# XBee_Explorer_Thin.net
KiCad netlist of a schematic drawn in EAGLE
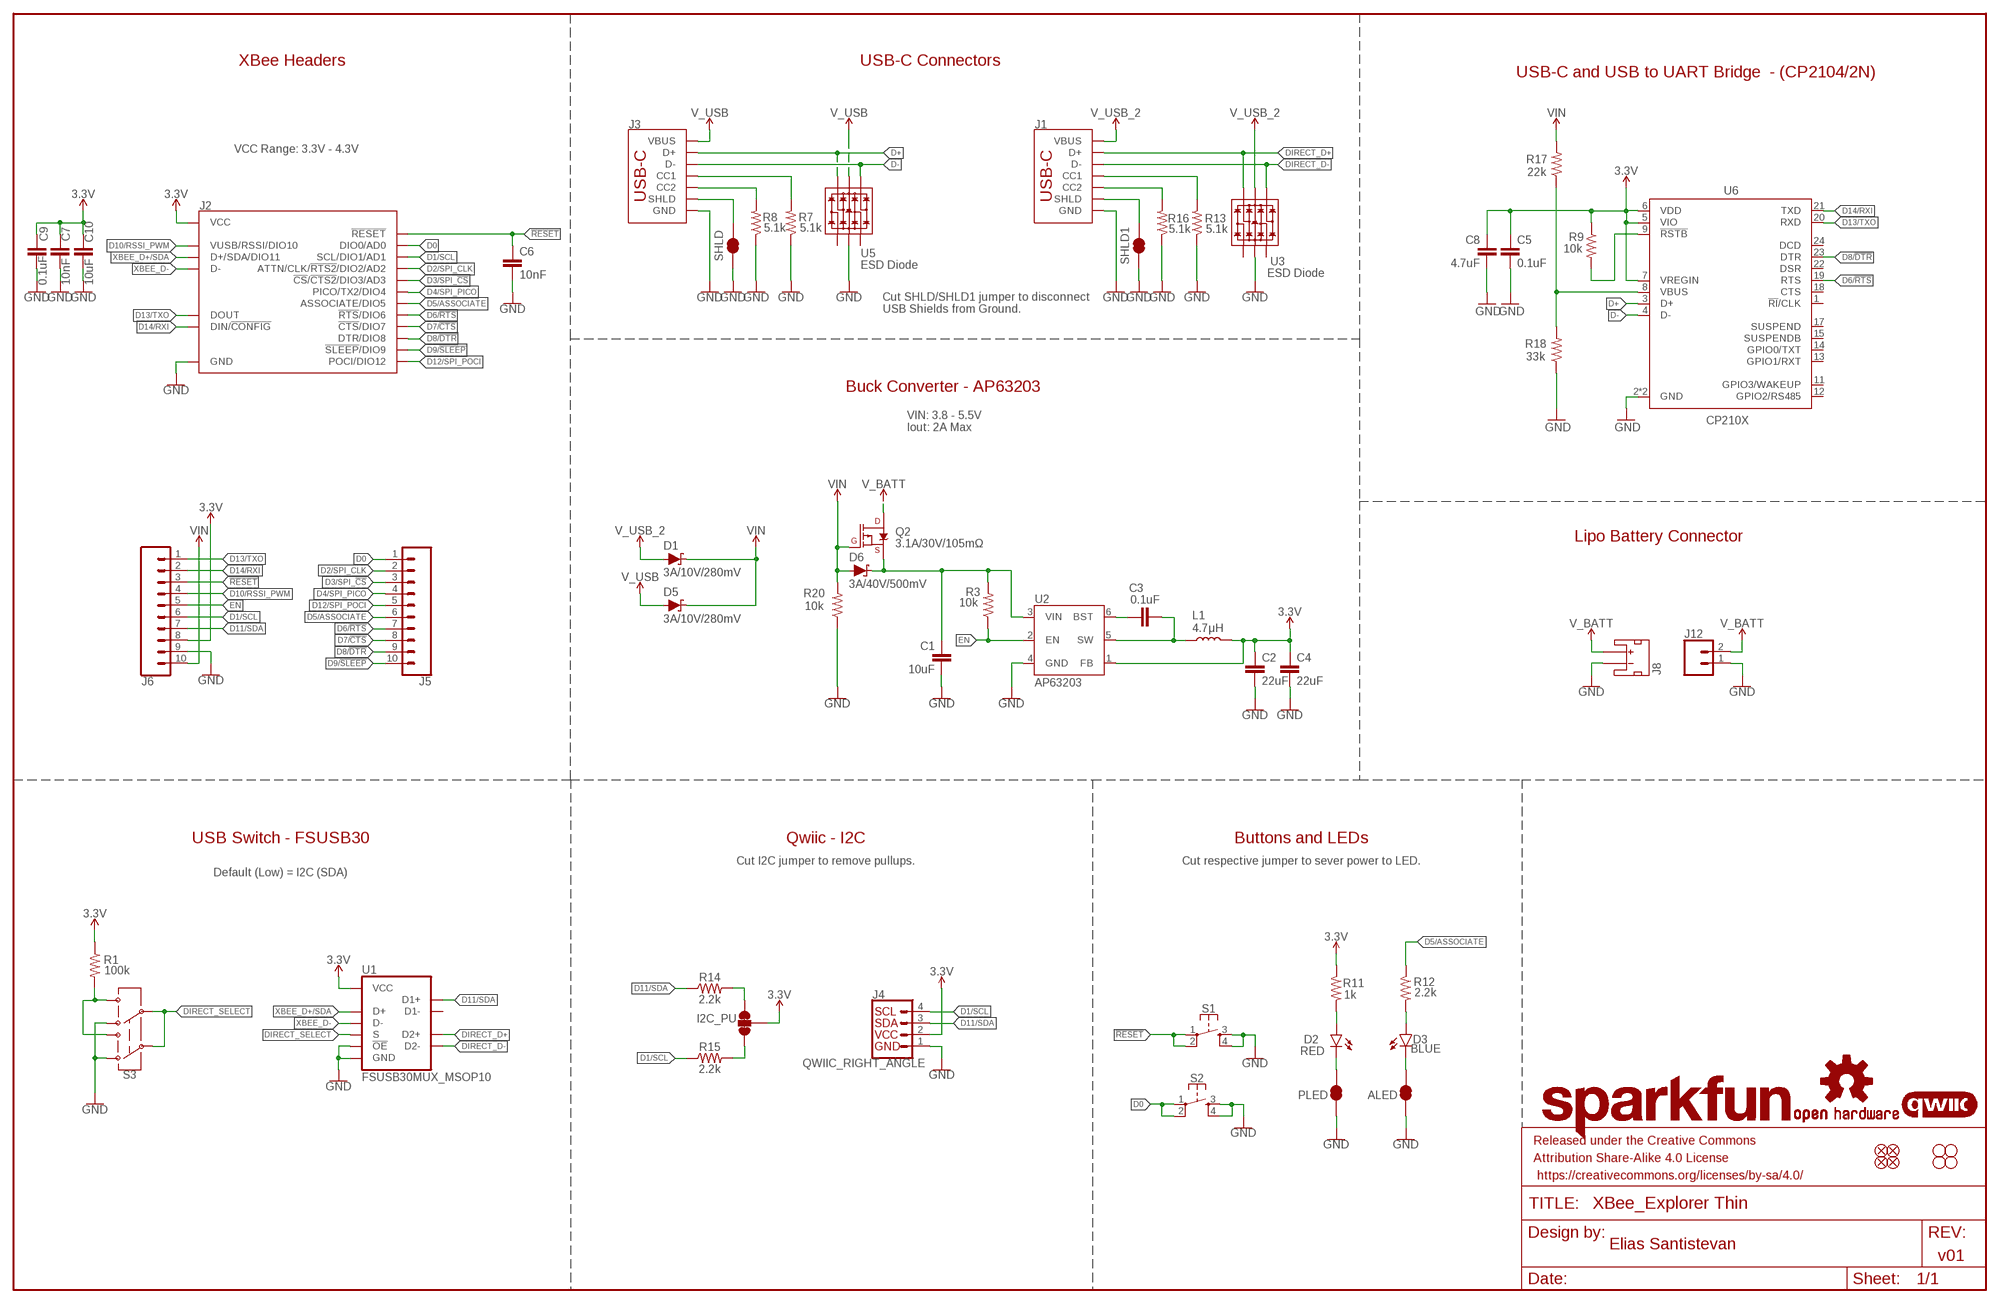
[diagram p0: schematic, sheet 1]

(export (version "E")
  (design (tool "Eeschema 10.0.6"))
  (components
    (comp (ref "ALED")
      (value "JUMPER-SMT_2_NC_TRACE_SILK")
      (footprint "eagle-import:SMT-JUMPER_2_NC_TRACE_SILK")
      (libsource (lib "eagle-import") (part "JUMPER-SMT_2_NC_TRACE_SILK"))
    )
    (comp (ref "C1")
      (value "10uF")
      (footprint "eagle-import:1210")
      (libsource (lib "eagle-import") (part "10UF-1210-50V-20%"))
    )
    (comp (ref "C2")
      (value "22uF")
      (footprint "eagle-import:0603")
      (libsource (lib "eagle-import") (part "22UF-0603-6.3V-20%"))
    )
    (comp (ref "C3")
      (value "0.1uF")
      (footprint "eagle-import:0603")
      (libsource (lib "eagle-import") (part "0.1UF-0603-25V-5%"))
    )
    (comp (ref "C4")
      (value "22uF")
      (footprint "eagle-import:0603")
      (libsource (lib "eagle-import") (part "22UF-0603-6.3V-20%"))
    )
    (comp (ref "C5")
      (value "0.1uF")
      (footprint "eagle-import:0603")
      (libsource (lib "eagle-import") (part "0.1UF-0603-25V-(+80/-20%)"))
    )
    (comp (ref "C6")
      (value "10nF")
      (footprint "eagle-import:0603")
      (libsource (lib "eagle-import") (part "10NF-0603-50V-10%"))
    )
    (comp (ref "C7")
      (value "10nF")
      (footprint "eagle-import:0603")
      (libsource (lib "eagle-import") (part "10NF-0603-50V-10%"))
    )
    (comp (ref "C8")
      (value "4.7uF")
      (footprint "eagle-import:0603")
      (libsource (lib "eagle-import") (part "4.7UF-0603-6.3V-(10%)"))
    )
    (comp (ref "C9")
      (value "0.1uF")
      (footprint "eagle-import:0603")
      (libsource (lib "eagle-import") (part "0.1UF-0603-25V-(+80/-20%)"))
    )
    (comp (ref "C10")
      (value "10uF")
      (footprint "eagle-import:0603")
      (libsource (lib "eagle-import") (part "10UF-0603-6.3V-20%"))
    )
    (comp (ref "D1")
      (value "3A/10V/280mV")
      (footprint "eagle-import:SOD-323")
      (libsource (lib "eagle-import") (part "DIODE-SCHOTTKY-BAT60A"))
    )
    (comp (ref "D2")
      (value "RED")
      (footprint "eagle-import:LED-0603")
      (libsource (lib "eagle-import") (part "LED-RED0603"))
    )
    (comp (ref "D3")
      (value "BLUE")
      (footprint "eagle-import:LED-0603")
      (libsource (lib "eagle-import") (part "LED-BLUE0603"))
    )
    (comp (ref "D5")
      (value "3A/10V/280mV")
      (footprint "eagle-import:SOD-323")
      (libsource (lib "eagle-import") (part "DIODE-SCHOTTKY-BAT60A"))
    )
    (comp (ref "D6")
      (value "3A/40V/500mV")
      (footprint "eagle-import:SMA-DIODE")
      (libsource (lib "eagle-import") (part "DIODE-SCHOTTKY-B340A"))
    )
    (comp (ref "FD1")
      (value "FIDUCIAL1X2")
      (footprint "eagle-import:FIDUCIAL-1X2")
      (libsource (lib "eagle-import") (part "FIDUCIAL1X2"))
    )
    (comp (ref "FD2")
      (value "FIDUCIAL1X2")
      (footprint "eagle-import:FIDUCIAL-1X2")
      (libsource (lib "eagle-import") (part "FIDUCIAL1X2"))
    )
    (comp (ref "FD3")
      (value "FIDUCIAL1X2")
      (footprint "eagle-import:FIDUCIAL-1X2")
      (libsource (lib "eagle-import") (part "FIDUCIAL1X2"))
    )
    (comp (ref "FD4")
      (value "FIDUCIAL1X2")
      (footprint "eagle-import:FIDUCIAL-1X2")
      (libsource (lib "eagle-import") (part "FIDUCIAL1X2"))
    )
    (comp (ref "FRAME1")
      (value "FRAME-LEDGER")
      (footprint "eagle-import:CREATIVE_COMMONS")
      (libsource (lib "eagle-import") (part "FRAME-LEDGER"))
    )
    (comp (ref "H1")
      (value "STAND-OFFTIGHT")
      (footprint "eagle-import:STAND-OFF-TIGHT")
      (libsource (lib "eagle-import") (part "STAND-OFFTIGHT"))
    )
    (comp (ref "H2")
      (value "STAND-OFFTIGHT")
      (footprint "eagle-import:STAND-OFF-TIGHT")
      (libsource (lib "eagle-import") (part "STAND-OFFTIGHT"))
    )
    (comp (ref "H3")
      (value "STAND-OFFTIGHT")
      (footprint "eagle-import:STAND-OFF-TIGHT")
      (libsource (lib "eagle-import") (part "STAND-OFFTIGHT"))
    )
    (comp (ref "H4")
      (value "STAND-OFFTIGHT")
      (footprint "eagle-import:STAND-OFF-TIGHT")
      (libsource (lib "eagle-import") (part "STAND-OFFTIGHT"))
    )
    (comp (ref "I2C_PU")
      (value "JUMPER-SMT_3_2-NC_TRACE_SILK")
      (footprint "eagle-import:SMT-JUMPER_3_2-NC_TRACE_SILK")
      (libsource (lib "eagle-import") (part "JUMPER-SMT_3_2-NC_TRACE_SILK"))
    )
    (comp (ref "J1")
      (value "USB_C_2-LAYER_PADS")
      (footprint "eagle-import:USB-C-16P-2LAYER-PADS")
      (libsource (lib "eagle-import") (part "USB_C_2-LAYER_PADS"))
    )
    (comp (ref "J2")
      (value "XBEE_UPDATEXBEE_SMD")
      (footprint "eagle-import:XBEE-SMD_SILK")
      (libsource (lib "eagle-import") (part "XBEE_UPDATEXBEE_SMD"))
    )
    (comp (ref "J3")
      (value "USB_C_2-LAYER_PADS")
      (footprint "eagle-import:USB-C-16P-2LAYER-PADS")
      (libsource (lib "eagle-import") (part "USB_C_2-LAYER_PADS"))
    )
    (comp (ref "J4")
      (value "QWIIC_RIGHT_ANGLE")
      (footprint "eagle-import:JST04_1MM_RA")
      (libsource (lib "eagle-import") (part "QWIIC_CONNECTORJS-1MM"))
    )
    (comp (ref "J5")
      (value "CONN_10NO_SILK_PTH_FEMALE")
      (footprint "eagle-import:1X10_NO_SILK")
      (libsource (lib "eagle-import") (part "CONN_10NO_SILK_PTH_FEMALE"))
    )
    (comp (ref "J6")
      (value "CONN_10NO_SILK_PTH_FEMALE")
      (footprint "eagle-import:1X10_NO_SILK")
      (libsource (lib "eagle-import") (part "CONN_10NO_SILK_PTH_FEMALE"))
    )
    (comp (ref "J8")
      (value "JST_2MM_MALE")
      (footprint "eagle-import:JST-2-SMD")
      (libsource (lib "eagle-import") (part "JST_2MM_MALE"))
    )
    (comp (ref "J12")
      (value "CONN_021X02_NO_SILK")
      (footprint "eagle-import:1X02_NO_SILK")
      (libsource (lib "eagle-import") (part "CONN_021X02_NO_SILK"))
    )
    (comp (ref "L1")
      (value "4.7μH")
      (footprint "eagle-import:INDUCTOR_4X4MM")
      (libsource (lib "eagle-import") (part "4.7μH_SHIELDED_INDUCTORNPIS_LS"))
    )
    (comp (ref "LOGO1")
      (value "SFE_LOGO_NAME.1_INCH")
      (footprint "eagle-import:SFE_LOGO_NAME_.1")
      (libsource (lib "eagle-import") (part "SFE_LOGO_NAME.1_INCH"))
    )
    (comp (ref "LOGO2")
      (value "OSHW-LOGOS")
      (footprint "eagle-import:OSHW-LOGO-S")
      (libsource (lib "eagle-import") (part "OSHW-LOGOS"))
    )
    (comp (ref "LOGO3")
      (value "QWIIC_LOGO_5MM")
      (footprint "eagle-import:QWIIC_5MM")
      (libsource (lib "eagle-import") (part "QWIIC_LOGO_5MM"))
    )
    (comp (ref "PLED")
      (value "JUMPER-SMT_2_NC_TRACE_SILK")
      (footprint "eagle-import:SMT-JUMPER_2_NC_TRACE_SILK")
      (libsource (lib "eagle-import") (part "JUMPER-SMT_2_NC_TRACE_SILK"))
    )
    (comp (ref "Q2")
      (value "3.1A/30V/105mΩ")
      (footprint "eagle-import:SOT23-3")
      (libsource (lib "eagle-import") (part "MOSFET_PCH-DMG2307L"))
    )
    (comp (ref "R1")
      (value "100k")
      (footprint "eagle-import:0603")
      (libsource (lib "eagle-import") (part "100KOHM-0603-1/10W-1%"))
    )
    (comp (ref "R3")
      (value "10k")
      (footprint "eagle-import:0603")
      (libsource (lib "eagle-import") (part "10KOHM-0603-1/10W-1%"))
    )
    (comp (ref "R7")
      (value "5.1k")
      (footprint "eagle-import:0603")
      (libsource (lib "eagle-import") (part "5.1KOHM5.1KOHM-0603-1/10W-1%"))
    )
    (comp (ref "R8")
      (value "5.1k")
      (footprint "eagle-import:0603")
      (libsource (lib "eagle-import") (part "5.1KOHM5.1KOHM-0603-1/10W-1%"))
    )
    (comp (ref "R9")
      (value "10k")
      (footprint "eagle-import:0603")
      (libsource (lib "eagle-import") (part "10KOHM-0603-1/10W-1%"))
    )
    (comp (ref "R11")
      (value "1k")
      (footprint "eagle-import:0603")
      (libsource (lib "eagle-import") (part "1KOHM-0603-1/10W-1%"))
    )
    (comp (ref "R12")
      (value "2.2k")
      (footprint "eagle-import:0603")
      (libsource (lib "eagle-import") (part "2.2KOHM-0603-1/10W-1%"))
    )
    (comp (ref "R13")
      (value "5.1k")
      (footprint "eagle-import:0603")
      (libsource (lib "eagle-import") (part "5.1KOHM5.1KOHM-0603-1/10W-1%"))
    )
    (comp (ref "R14")
      (value "2.2k")
      (footprint "eagle-import:0603")
      (libsource (lib "eagle-import") (part "2.2KOHM-0603-1/10W-1%"))
    )
    (comp (ref "R15")
      (value "2.2k")
      (footprint "eagle-import:0603")
      (libsource (lib "eagle-import") (part "2.2KOHM-0603-1/10W-1%"))
    )
    (comp (ref "R16")
      (value "5.1k")
      (footprint "eagle-import:0603")
      (libsource (lib "eagle-import") (part "5.1KOHM5.1KOHM-0603-1/10W-1%"))
    )
    (comp (ref "R17")
      (value "22k")
      (footprint "eagle-import:0603")
      (libsource (lib "eagle-import") (part "22KOHM-0603-1/10W-1%"))
    )
    (comp (ref "R18")
      (value "33k")
      (footprint "eagle-import:0603")
      (libsource (lib "eagle-import") (part "33KOHM-0603-1/10W-1%"))
    )
    (comp (ref "R20")
      (value "10k")
      (footprint "eagle-import:0603")
      (libsource (lib "eagle-import") (part "10KOHM-0603-1/10W-1%"))
    )
    (comp (ref "S1")
      (value "MOMENTARY-SWITCH-SPST-2-SMD-5.2MM-TALL")
      (footprint "eagle-import:TACTILE_SWITCH_SMD_5.2MM")
      (libsource (lib "eagle-import") (part "MOMENTARY-SWITCH-SPST-2-SMD-5.2MM-TALL"))
    )
    (comp (ref "S2")
      (value "MOMENTARY-SWITCH-SPST-2-SMD-5.2MM-TALL")
      (footprint "eagle-import:TACTILE_SWITCH_SMD_5.2MM")
      (libsource (lib "eagle-import") (part "MOMENTARY-SWITCH-SPST-2-SMD-5.2MM-TALL"))
    )
    (comp (ref "S3")
      (value "SWITCH-DPDT-SMD-AYZ0202")
      (footprint "eagle-import:SWITCH_DPDT_SMD_AYZ0202")
      (libsource (lib "eagle-import") (part "SWITCH-DPDT-SMD-AYZ0202"))
    )
    (comp (ref "SHLD")
      (value "JUMPER-SMT_2_NC_TRACE_SILK")
      (footprint "eagle-import:SMT-JUMPER_2_NC_TRACE_SILK")
      (libsource (lib "eagle-import") (part "JUMPER-SMT_2_NC_TRACE_SILK"))
    )
    (comp (ref "SHLD1")
      (value "JUMPER-SMT_2_NC_TRACE_SILK")
      (footprint "eagle-import:SMT-JUMPER_2_NC_TRACE_SILK")
      (libsource (lib "eagle-import") (part "JUMPER-SMT_2_NC_TRACE_SILK"))
    )
    (comp (ref "U1")
      (value "FSUSB30MUX_MSOP10")
      (footprint "eagle-import:MSOP10")
      (libsource (lib "eagle-import") (part "FSUSB30MUX_MSOP10"))
    )
    (comp (ref "U2")
      (value "AP63203")
      (footprint "eagle-import:SOT23-6")
      (libsource (lib "eagle-import") (part "AP63203"))
    )
    (comp (ref "U3")
      (value "ESD Diode")
      (footprint "eagle-import:SOT-23-6")
      (libsource (lib "eagle-import") (part "TVS_DIODE_ARRAY_DT1042-04SO-7"))
    )
    (comp (ref "U5")
      (value "ESD Diode")
      (footprint "eagle-import:SOT-23-6")
      (libsource (lib "eagle-import") (part "TVS_DIODE_ARRAY_DT1042-04SO-7"))
    )
    (comp (ref "U6")
      (value "CP210X")
      (footprint "eagle-import:QFN24")
      (libsource (lib "eagle-import") (part "CP2102N"))
    )
  )
  (nets
    (net (code "1") (name "/D3{slash}SPI_~{CS}") (class "Default")
      (node (ref "J2") (pin "17") (pinfunction "~{CS}/~{CTS2}/DIO3/AD3_17") (pintype "bidirectional"))
      (node (ref "J5") (pin "3") (pinfunction "3_3") (pintype "passive"))
    )
    (net (code "2") (name "/D6{slash}~{RTS}") (class "Default")
      (node (ref "J2") (pin "16") (pinfunction "~{RTS}/DIO6_16") (pintype "input"))
      (node (ref "J5") (pin "7") (pinfunction "7_7") (pintype "passive"))
      (node (ref "U6") (pin "19") (pinfunction "RTS_19") (pintype "bidirectional"))
    )
    (net (code "3") (name "/D7{slash}~{CTS}") (class "Default")
      (node (ref "J2") (pin "12") (pinfunction "~{CTS}/DIO7_12") (pintype "output"))
      (node (ref "J5") (pin "8") (pinfunction "8_8") (pintype "passive"))
    )
    (net (code "4") (name "/D8{slash}~{DTR}") (class "Default")
      (node (ref "J2") (pin "9") (pinfunction "DTR/DIO8_9") (pintype "bidirectional"))
      (node (ref "J5") (pin "9") (pinfunction "9_9") (pintype "passive"))
      (node (ref "U6") (pin "23") (pinfunction "DTR_23") (pintype "bidirectional"))
    )
    (net (code "5") (name "/D9{slash}~{SLEEP}") (class "Default")
      (node (ref "J2") (pin "13") (pinfunction "~{SLEEP}/DIO9_13") (pintype "bidirectional"))
      (node (ref "J5") (pin "10") (pinfunction "10_10") (pintype "passive"))
    )
    (net (code "6") (name "/~{RESET}") (class "Default")
      (node (ref "C6") (pin "1") (pinfunction "1_1") (pintype "passive"))
      (node (ref "J2") (pin "5") (pinfunction "~{RESET}_5") (pintype "input"))
      (node (ref "J6") (pin "3") (pinfunction "3_3") (pintype "passive"))
      (node (ref "S1") (pin "1") (pinfunction "1_1") (pintype "passive"))
      (node (ref "S1") (pin "2") (pinfunction "2_2") (pintype "passive"))
    )
    (net (code "7") (name "3.3V") (class "Default")
      (node (ref "C10") (pin "1") (pinfunction "1_1") (pintype "passive"))
      (node (ref "C2") (pin "1") (pinfunction "1_1") (pintype "passive"))
      (node (ref "C4") (pin "1") (pinfunction "1_1") (pintype "passive"))
      (node (ref "C5") (pin "1") (pinfunction "1_1") (pintype "passive"))
      (node (ref "C7") (pin "1") (pinfunction "1_1") (pintype "passive"))
      (node (ref "C8") (pin "1") (pinfunction "1_1") (pintype "passive"))
      (node (ref "C9") (pin "1") (pinfunction "1_1") (pintype "passive"))
      (node (ref "I2C_PU") (pin "2") (pinfunction "2_2") (pintype "passive"))
      (node (ref "J2") (pin "1") (pinfunction "VCC_1") (pintype "power_in"))
      (node (ref "J4") (pin "2") (pinfunction "2_2") (pintype "power_in"))
      (node (ref "J6") (pin "8") (pinfunction "8_8") (pintype "passive"))
      (node (ref "L1") (pin "P$2") (pinfunction "2_P$2") (pintype "passive"))
      (node (ref "R1") (pin "1") (pinfunction "1_1") (pintype "passive"))
      (node (ref "R11") (pin "1") (pinfunction "1_1") (pintype "passive"))
      (node (ref "R9") (pin "1") (pinfunction "1_1") (pintype "passive"))
      (node (ref "U1") (pin "10") (pinfunction "VCC_10") (pintype "bidirectional"))
      (node (ref "U2") (pin "1") (pinfunction "FB_1") (pintype "bidirectional"))
      (node (ref "U6") (pin "5") (pinfunction "VIO_5") (pintype "bidirectional"))
      (node (ref "U6") (pin "6") (pinfunction "VDD_6") (pintype "bidirectional"))
      (node (ref "U6") (pin "7") (pinfunction "VREGIN_7") (pintype "bidirectional"))
    )
    (net (code "8") (name "D+") (class "Default")
      (node (ref "J3") (pin "A6") (pinfunction "D+_A6") (pintype "bidirectional"))
      (node (ref "J3") (pin "B6") (pinfunction "D+_B6") (pintype "bidirectional"))
      (node (ref "U5") (pin "6") (pinfunction "IO4_6") (pintype "bidirectional"))
      (node (ref "U6") (pin "3") (pinfunction "D+_3") (pintype "bidirectional"))
    )
    (net (code "9") (name "D-") (class "Default")
      (node (ref "J3") (pin "A7") (pinfunction "D-_A7") (pintype "bidirectional"))
      (node (ref "J3") (pin "B7") (pinfunction "D-_B7") (pintype "bidirectional"))
      (node (ref "U5") (pin "4") (pinfunction "IO3_4") (pintype "bidirectional"))
      (node (ref "U6") (pin "4") (pinfunction "D-_4") (pintype "bidirectional"))
    )
    (net (code "10") (name "D0") (class "Default")
      (node (ref "J2") (pin "20") (pinfunction "DIO0/AD0_20") (pintype "bidirectional"))
      (node (ref "J5") (pin "1") (pinfunction "1_1") (pintype "passive"))
      (node (ref "S2") (pin "1") (pinfunction "1_1") (pintype "passive"))
      (node (ref "S2") (pin "2") (pinfunction "2_2") (pintype "passive"))
    )
    (net (code "11") (name "D1{slash}SCL") (class "Default")
      (node (ref "J2") (pin "19") (pinfunction "SCL/DIO1/AD1_19") (pintype "bidirectional"))
      (node (ref "J4") (pin "4") (pinfunction "4_4") (pintype "passive"))
      (node (ref "J6") (pin "6") (pinfunction "6_6") (pintype "passive"))
      (node (ref "R15") (pin "1") (pinfunction "1_1") (pintype "passive"))
    )
    (net (code "12") (name "D2{slash}SPI_CLK") (class "Default")
      (node (ref "J2") (pin "18") (pinfunction "ATTN/CLK/~{RTS2}/DIO2/AD2_18") (pintype "bidirectional"))
      (node (ref "J5") (pin "2") (pinfunction "2_2") (pintype "passive"))
    )
    (net (code "13") (name "D4{slash}SPI_PICO") (class "Default")
      (node (ref "J2") (pin "11") (pinfunction "PICO/TX2/DIO4_11") (pintype "bidirectional"))
      (node (ref "J5") (pin "4") (pinfunction "4_4") (pintype "passive"))
    )
    (net (code "14") (name "D5{slash}ASSOCIATE") (class "Default")
      (node (ref "J2") (pin "15") (pinfunction "ASSOCIATE/DIO5_15") (pintype "bidirectional"))
      (node (ref "J5") (pin "6") (pinfunction "6_6") (pintype "passive"))
      (node (ref "R12") (pin "1") (pinfunction "1_1") (pintype "passive"))
    )
    (net (code "15") (name "D10{slash}RSSI_PWM") (class "Default")
      (node (ref "J2") (pin "6") (pinfunction "VUSB/RSSI/DIO10_6") (pintype "bidirectional"))
      (node (ref "J6") (pin "4") (pinfunction "4_4") (pintype "passive"))
    )
    (net (code "16") (name "D11{slash}SDA") (class "Default")
      (node (ref "J4") (pin "3") (pinfunction "3_3") (pintype "passive"))
      (node (ref "J6") (pin "7") (pinfunction "7_7") (pintype "passive"))
      (node (ref "R14") (pin "1") (pinfunction "1_1") (pintype "passive"))
      (node (ref "U1") (pin "2") (pinfunction "D1+_2") (pintype "bidirectional"))
    )
    (net (code "17") (name "D12{slash}SPI_POCI") (class "Default")
      (node (ref "J2") (pin "4") (pinfunction "POCI/DIO12_4") (pintype "bidirectional"))
      (node (ref "J5") (pin "5") (pinfunction "5_5") (pintype "passive"))
    )
    (net (code "18") (name "D13{slash}TXO") (class "Default")
      (node (ref "J2") (pin "2") (pinfunction "DOUT_2") (pintype "output"))
      (node (ref "J6") (pin "1") (pinfunction "1_1") (pintype "passive"))
      (node (ref "U6") (pin "20") (pinfunction "RXD_20") (pintype "bidirectional"))
    )
    (net (code "19") (name "D14{slash}RXI") (class "Default")
      (node (ref "J2") (pin "3") (pinfunction "DIN/~{CONFIG}_3") (pintype "input"))
      (node (ref "J6") (pin "2") (pinfunction "2_2") (pintype "passive"))
      (node (ref "U6") (pin "21") (pinfunction "TXD_21") (pintype "bidirectional"))
    )
    (net (code "20") (name "DIRECT_D+") (class "Default")
      (node (ref "J1") (pin "A6") (pinfunction "D+_A6") (pintype "bidirectional"))
      (node (ref "J1") (pin "B6") (pinfunction "D+_B6") (pintype "bidirectional"))
      (node (ref "U1") (pin "3") (pinfunction "D2+_3") (pintype "bidirectional"))
      (node (ref "U3") (pin "6") (pinfunction "IO4_6") (pintype "bidirectional"))
    )
    (net (code "21") (name "DIRECT_D-") (class "Default")
      (node (ref "J1") (pin "A7") (pinfunction "D-_A7") (pintype "bidirectional"))
      (node (ref "J1") (pin "B7") (pinfunction "D-_B7") (pintype "bidirectional"))
      (node (ref "U1") (pin "7") (pinfunction "D2-_7") (pintype "bidirectional"))
      (node (ref "U3") (pin "4") (pinfunction "IO3_4") (pintype "bidirectional"))
    )
    (net (code "22") (name "DIRECT_SELECT") (class "Default")
      (node (ref "S3") (pin "2") (pinfunction "2_2") (pintype "bidirectional"))
      (node (ref "S3") (pin "5") (pinfunction "5_5") (pintype "bidirectional"))
      (node (ref "U1") (pin "1") (pinfunction "S_1") (pintype "bidirectional"))
    )
    (net (code "23") (name "EN") (class "Default")
      (node (ref "J6") (pin "5") (pinfunction "5_5") (pintype "passive"))
      (node (ref "R3") (pin "1") (pinfunction "1_1") (pintype "passive"))
      (node (ref "U2") (pin "2") (pinfunction "EN_2") (pintype "bidirectional"))
    )
    (net (code "24") (name "GND") (class "Default")
      (node (ref "ALED") (pin "1") (pinfunction "1_1") (pintype "passive"))
      (node (ref "C1") (pin "2") (pinfunction "2_2") (pintype "passive"))
      (node (ref "C10") (pin "2") (pinfunction "2_2") (pintype "passive"))
      (node (ref "C2") (pin "2") (pinfunction "2_2") (pintype "passive"))
      (node (ref "C4") (pin "2") (pinfunction "2_2") (pintype "passive"))
      (node (ref "C5") (pin "2") (pinfunction "2_2") (pintype "passive"))
      (node (ref "C6") (pin "2") (pinfunction "2_2") (pintype "passive"))
      (node (ref "C7") (pin "2") (pinfunction "2_2") (pintype "passive"))
      (node (ref "C8") (pin "2") (pinfunction "2_2") (pintype "passive"))
      (node (ref "C9") (pin "2") (pinfunction "2_2") (pintype "passive"))
      (node (ref "J1") (pin "GND") (pinfunction "GND_GND") (pintype "bidirectional"))
      (node (ref "J1") (pin "GND2") (pinfunction "GND_GND2") (pintype "bidirectional"))
      (node (ref "J12") (pin "1") (pinfunction "1_1") (pintype "passive"))
      (node (ref "J2") (pin "10") (pinfunction "GND_10") (pintype "power_in"))
      (node (ref "J3") (pin "GND") (pinfunction "GND_GND") (pintype "bidirectional"))
      (node (ref "J3") (pin "GND2") (pinfunction "GND_GND2") (pintype "bidirectional"))
      (node (ref "J4") (pin "1") (pinfunction "1_1") (pintype "power_in"))
      (node (ref "J6") (pin "9") (pinfunction "9_9") (pintype "passive"))
      (node (ref "J8") (pin "1") (pinfunction "-_1") (pintype "bidirectional"))
      (node (ref "PLED") (pin "1") (pinfunction "1_1") (pintype "passive"))
      (node (ref "R13") (pin "1") (pinfunction "1_1") (pintype "passive"))
      (node (ref "R16") (pin "1") (pinfunction "1_1") (pintype "passive"))
      (node (ref "R18") (pin "1") (pinfunction "1_1") (pintype "passive"))
      (node (ref "R20") (pin "1") (pinfunction "1_1") (pintype "passive"))
      (node (ref "R7") (pin "1") (pinfunction "1_1") (pintype "passive"))
      (node (ref "R8") (pin "1") (pinfunction "1_1") (pintype "passive"))
      (node (ref "S1") (pin "3") (pinfunction "3_3") (pintype "passive"))
      (node (ref "S1") (pin "4") (pinfunction "4_4") (pintype "passive"))
      (node (ref "S2") (pin "3") (pinfunction "3_3") (pintype "passive"))
      (node (ref "S2") (pin "4") (pinfunction "4_4") (pintype "passive"))
      (node (ref "S3") (pin "3") (pinfunction "3_3") (pintype "bidirectional"))
      (node (ref "S3") (pin "6") (pinfunction "6_6") (pintype "bidirectional"))
      (node (ref "SHLD") (pin "1") (pinfunction "1_1") (pintype "passive"))
      (node (ref "SHLD1") (pin "1") (pinfunction "1_1") (pintype "passive"))
      (node (ref "U1") (pin "5") (pinfunction "GND_5") (pintype "bidirectional"))
      (node (ref "U1") (pin "9") (pinfunction "~{OE}_9") (pintype "bidirectional"))
      (node (ref "U2") (pin "4") (pinfunction "GND_4") (pintype "bidirectional"))
      (node (ref "U3") (pin "2") (pinfunction "VSS_2") (pintype "bidirectional"))
      (node (ref "U5") (pin "2") (pinfunction "VSS_2") (pintype "bidirectional"))
      (node (ref "U6") (pin "2") (pinfunction "GND_2") (pintype "bidirectional"))
      (node (ref "U6") (pin "PAD") (pinfunction "GND_PAD") (pintype "bidirectional"))
    )
    (net (code "25") (name "Net-(ALED-Pad2)") (class "Default")
      (node (ref "ALED") (pin "2") (pinfunction "2_2") (pintype "passive"))
      (node (ref "D3") (pin "C") (pinfunction "C_C") (pintype "passive"))
    )
    (net (code "26") (name "Net-(D2-PadA)") (class "Default")
      (node (ref "D2") (pin "A") (pinfunction "A_A") (pintype "passive"))
      (node (ref "R11") (pin "2") (pinfunction "2_2") (pintype "passive"))
    )
    (net (code "27") (name "Net-(D2-PadC)") (class "Default")
      (node (ref "D2") (pin "C") (pinfunction "C_C") (pintype "passive"))
      (node (ref "PLED") (pin "2") (pinfunction "2_2") (pintype "passive"))
    )
    (net (code "28") (name "Net-(D3-PadA)") (class "Default")
      (node (ref "D3") (pin "A") (pinfunction "A_A") (pintype "passive"))
      (node (ref "R12") (pin "2") (pinfunction "2_2") (pintype "passive"))
    )
    (net (code "29") (name "Net-(I2C_PU-Pad1)") (class "Default")
      (node (ref "I2C_PU") (pin "1") (pinfunction "1_1") (pintype "passive"))
      (node (ref "R15") (pin "2") (pinfunction "2_2") (pintype "passive"))
    )
    (net (code "30") (name "Net-(I2C_PU-Pad3)") (class "Default")
      (node (ref "I2C_PU") (pin "3") (pinfunction "3_3") (pintype "passive"))
      (node (ref "R14") (pin "2") (pinfunction "2_2") (pintype "passive"))
    )
    (net (code "31") (name "Net-(J1-CC1)") (class "Default")
      (node (ref "J1") (pin "A5") (pinfunction "CC1_A5") (pintype "bidirectional"))
      (node (ref "R13") (pin "2") (pinfunction "2_2") (pintype "passive"))
    )
    (net (code "32") (name "Net-(J1-CC2)") (class "Default")
      (node (ref "J1") (pin "B5") (pinfunction "CC2_B5") (pintype "bidirectional"))
      (node (ref "R16") (pin "2") (pinfunction "2_2") (pintype "passive"))
    )
    (net (code "33") (name "Net-(J1-SHLD-PadSHLD1)") (class "Default")
      (node (ref "J1") (pin "SHLD1") (pinfunction "SHLD_SHLD1") (pintype "bidirectional"))
      (node (ref "J1") (pin "SHLD2") (pinfunction "SHLD_SHLD2") (pintype "bidirectional"))
      (node (ref "J1") (pin "SHLD3") (pinfunction "SHLD_SHLD3") (pintype "bidirectional"))
      (node (ref "J1") (pin "SHLD4") (pinfunction "SHLD_SHLD4") (pintype "bidirectional"))
      (node (ref "SHLD1") (pin "2") (pinfunction "2_2") (pintype "passive"))
    )
    (net (code "34") (name "Net-(J3-CC1)") (class "Default")
      (node (ref "J3") (pin "A5") (pinfunction "CC1_A5") (pintype "bidirectional"))
      (node (ref "R7") (pin "2") (pinfunction "2_2") (pintype "passive"))
    )
    (net (code "35") (name "Net-(J3-CC2)") (class "Default")
      (node (ref "J3") (pin "B5") (pinfunction "CC2_B5") (pintype "bidirectional"))
      (node (ref "R8") (pin "2") (pinfunction "2_2") (pintype "passive"))
    )
    (net (code "36") (name "Net-(J3-SHLD-PadSHLD1)") (class "Default")
      (node (ref "J3") (pin "SHLD1") (pinfunction "SHLD_SHLD1") (pintype "bidirectional"))
      (node (ref "J3") (pin "SHLD2") (pinfunction "SHLD_SHLD2") (pintype "bidirectional"))
      (node (ref "J3") (pin "SHLD3") (pinfunction "SHLD_SHLD3") (pintype "bidirectional"))
      (node (ref "J3") (pin "SHLD4") (pinfunction "SHLD_SHLD4") (pintype "bidirectional"))
      (node (ref "SHLD") (pin "2") (pinfunction "2_2") (pintype "passive"))
    )
    (net (code "37") (name "Net-(L1-1)") (class "Default")
      (node (ref "C3") (pin "2") (pinfunction "2_2") (pintype "passive"))
      (node (ref "L1") (pin "P$1") (pinfunction "1_P$1") (pintype "passive"))
      (node (ref "U2") (pin "5") (pinfunction "SW_5") (pintype "bidirectional"))
    )
    (net (code "38") (name "Net-(Q2-S)") (class "Default")
      (node (ref "C1") (pin "1") (pinfunction "1_1") (pintype "passive"))
      (node (ref "D6") (pin "C") (pinfunction "C_C") (pintype "passive"))
      (node (ref "Q2") (pin "2") (pinfunction "S_2") (pintype "bidirectional"))
      (node (ref "R3") (pin "2") (pinfunction "2_2") (pintype "passive"))
      (node (ref "U2") (pin "3") (pinfunction "VIN_3") (pintype "bidirectional"))
    )
    (net (code "39") (name "Net-(R1-Pad2)") (class "Default")
      (node (ref "R1") (pin "2") (pinfunction "2_2") (pintype "passive"))
      (node (ref "S3") (pin "1") (pinfunction "1_1") (pintype "bidirectional"))
      (node (ref "S3") (pin "4") (pinfunction "4_4") (pintype "bidirectional"))
    )
    (net (code "40") (name "Net-(U2-BST)") (class "Default")
      (node (ref "C3") (pin "1") (pinfunction "1_1") (pintype "passive"))
      (node (ref "U2") (pin "6") (pinfunction "BST_6") (pintype "bidirectional"))
    )
    (net (code "41") (name "Net-(U6-VBUS)") (class "Default")
      (node (ref "R17") (pin "1") (pinfunction "1_1") (pintype "passive"))
      (node (ref "R18") (pin "2") (pinfunction "2_2") (pintype "passive"))
      (node (ref "U6") (pin "8") (pinfunction "VBUS_8") (pintype "bidirectional"))
    )
    (net (code "42") (name "Net-(U6-~{RSTB})") (class "Default")
      (node (ref "R9") (pin "2") (pinfunction "2_2") (pintype "passive"))
      (node (ref "U6") (pin "9") (pinfunction "~{RSTB}_9") (pintype "bidirectional"))
    )
    (net (code "43") (name "VIN") (class "Default")
      (node (ref "D1") (pin "C") (pinfunction "C_C") (pintype "passive"))
      (node (ref "D5") (pin "C") (pinfunction "C_C") (pintype "passive"))
      (node (ref "D6") (pin "A") (pinfunction "A_A") (pintype "passive"))
      (node (ref "J6") (pin "10") (pinfunction "10_10") (pintype "passive"))
      (node (ref "Q2") (pin "1") (pinfunction "G_1") (pintype "bidirectional"))
      (node (ref "R17") (pin "2") (pinfunction "2_2") (pintype "passive"))
      (node (ref "R20") (pin "2") (pinfunction "2_2") (pintype "passive"))
    )
    (net (code "44") (name "V_BATT") (class "Default")
      (node (ref "J12") (pin "2") (pinfunction "2_2") (pintype "passive"))
      (node (ref "J8") (pin "2") (pinfunction "+_2") (pintype "bidirectional"))
      (node (ref "Q2") (pin "3") (pinfunction "D_3") (pintype "bidirectional"))
    )
    (net (code "45") (name "V_USB") (class "Default")
      (node (ref "D5") (pin "A") (pinfunction "A_A") (pintype "passive"))
      (node (ref "J3") (pin "VBUS1") (pinfunction "VBUS_VBUS1") (pintype "bidirectional"))
      (node (ref "J3") (pin "VBUS2") (pinfunction "VBUS_VBUS2") (pintype "bidirectional"))
      (node (ref "U5") (pin "5") (pinfunction "VCC_5") (pintype "bidirectional"))
    )
    (net (code "46") (name "V_USB_2") (class "Default")
      (node (ref "D1") (pin "A") (pinfunction "A_A") (pintype "passive"))
      (node (ref "J1") (pin "VBUS1") (pinfunction "VBUS_VBUS1") (pintype "bidirectional"))
      (node (ref "J1") (pin "VBUS2") (pinfunction "VBUS_VBUS2") (pintype "bidirectional"))
      (node (ref "U3") (pin "5") (pinfunction "VCC_5") (pintype "bidirectional"))
    )
    (net (code "47") (name "XBEE_D+{slash}SDA") (class "Default")
      (node (ref "J2") (pin "7") (pinfunction "D+/SDA/DIO11_7") (pintype "bidirectional"))
      (node (ref "U1") (pin "4") (pinfunction "D+_4") (pintype "bidirectional"))
    )
    (net (code "48") (name "XBEE_D-") (class "Default")
      (node (ref "J2") (pin "8") (pinfunction "D-_8") (pintype "bidirectional"))
      (node (ref "U1") (pin "6") (pinfunction "D-_6") (pintype "bidirectional"))
    )
    (net (code "49") (name "unconnected-(J8-PAD1-PadNC1)") (class "Default")
      (node (ref "J8") (pin "NC1") (pinfunction "PAD1_NC1") (pintype "bidirectional"))
    )
    (net (code "50") (name "unconnected-(J8-PAD2-PadNC2)") (class "Default")
      (node (ref "J8") (pin "NC2") (pinfunction "PAD2_NC2") (pintype "bidirectional"))
    )
    (net (code "51") (name "unconnected-(U1-D1--Pad8)") (class "Default")
      (node (ref "U1") (pin "8") (pinfunction "D1-_8") (pintype "bidirectional"))
    )
    (net (code "52") (name "unconnected-(U3-IO1-Pad1)") (class "Default")
      (node (ref "U3") (pin "1") (pinfunction "IO1_1") (pintype "bidirectional"))
    )
    (net (code "53") (name "unconnected-(U3-IO2-Pad3)") (class "Default")
      (node (ref "U3") (pin "3") (pinfunction "IO2_3") (pintype "bidirectional"))
    )
    (net (code "54") (name "unconnected-(U5-IO1-Pad1)") (class "Default")
      (node (ref "U5") (pin "1") (pinfunction "IO1_1") (pintype "bidirectional"))
    )
    (net (code "55") (name "unconnected-(U5-IO2-Pad3)") (class "Default")
      (node (ref "U5") (pin "3") (pinfunction "IO2_3") (pintype "bidirectional"))
    )
    (net (code "56") (name "unconnected-(U6-CTS-Pad18)") (class "Default")
      (node (ref "U6") (pin "18") (pinfunction "CTS_18") (pintype "bidirectional"))
    )
    (net (code "57") (name "unconnected-(U6-DCD-Pad24)") (class "Default")
      (node (ref "U6") (pin "24") (pinfunction "DCD_24") (pintype "bidirectional"))
    )
    (net (code "58") (name "unconnected-(U6-DSR-Pad22)") (class "Default")
      (node (ref "U6") (pin "22") (pinfunction "DSR_22") (pintype "bidirectional"))
    )
    (net (code "59") (name "unconnected-(U6-GPIO0{slash}TXT-Pad14)") (class "Default")
      (node (ref "U6") (pin "14") (pinfunction "GPIO0/TXT_14") (pintype "bidirectional"))
    )
    (net (code "60") (name "unconnected-(U6-GPIO1{slash}RXT-Pad13)") (class "Default")
      (node (ref "U6") (pin "13") (pinfunction "GPIO1/RXT_13") (pintype "bidirectional"))
    )
    (net (code "61") (name "unconnected-(U6-GPIO2{slash}RS485-Pad12)") (class "Default")
      (node (ref "U6") (pin "12") (pinfunction "GPIO2/RS485_12") (pintype "bidirectional"))
    )
    (net (code "62") (name "unconnected-(U6-GPIO3{slash}WAKEUP-Pad11)") (class "Default")
      (node (ref "U6") (pin "11") (pinfunction "GPIO3/WAKEUP_11") (pintype "bidirectional"))
    )
    (net (code "63") (name "unconnected-(U6-SUSPEND-Pad17)") (class "Default")
      (node (ref "U6") (pin "17") (pinfunction "SUSPEND_17") (pintype "bidirectional"))
    )
    (net (code "64") (name "unconnected-(U6-SUSPENDB-Pad15)") (class "Default")
      (node (ref "U6") (pin "15") (pinfunction "SUSPENDB_15") (pintype "bidirectional"))
    )
    (net (code "65") (name "unconnected-(U6-~{RI}{slash}CLK-Pad1)") (class "Default")
      (node (ref "U6") (pin "1") (pinfunction "~{RI}/CLK_1") (pintype "bidirectional"))
    )
  )
)
